# Atmaca.net
KiCad netlist of a schematic drawn in Altium Designer
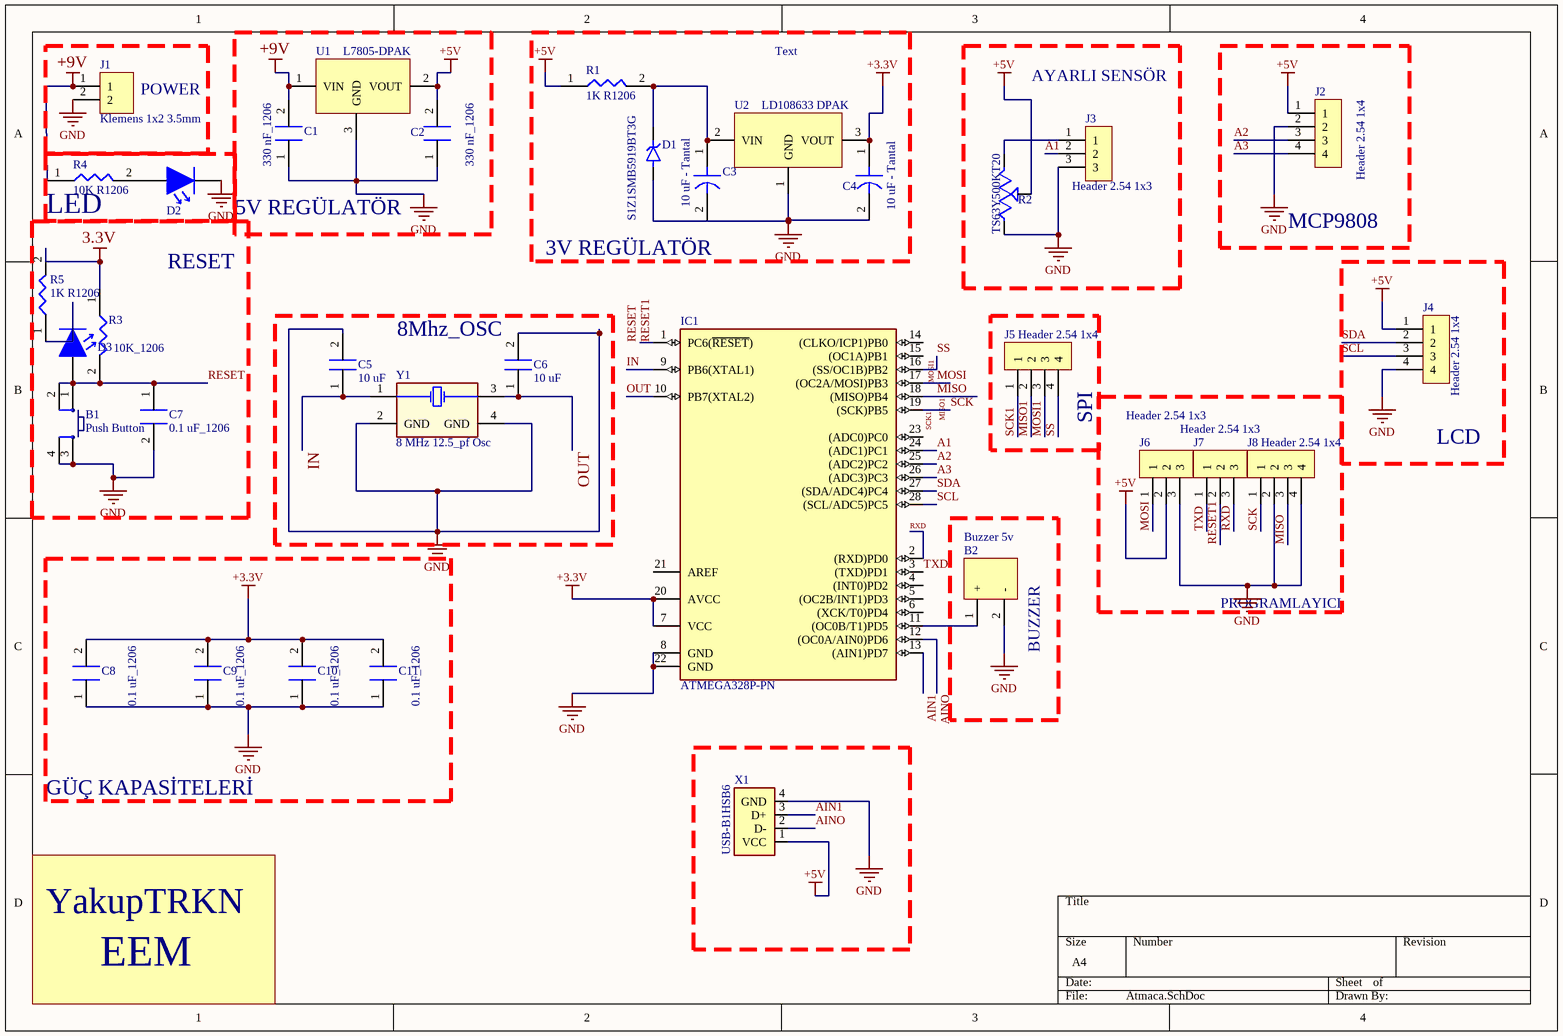
[diagram p0: Atmaca.SchDoc]

(export (version "E")
  (design (tool "Eeschema 10.0.6"))
  (components
    (comp (ref "B1")
      (value "Push Button")
      (footprint "PUSB BUTTON-SMD")
      (description "Smd Push Button")
      (libsource (lib "Staj") (part "Push Button"))
    )
    (comp (ref "B2")
      (value "Buzzer 5v")
      (footprint "Buzzer 5v")
      (libsource (lib "Atmaca") (part "Buzzer 5v"))
    )
    (comp (ref "C1")
      (value "330 nF_1206")
      (footprint "C1206")
      (description "330 nF C1206")
      (libsource (lib "Atmaca") (part "330 nF C1206"))
    )
    (comp (ref "C2")
      (value "330 nF_1206")
      (footprint "C1206")
      (description "330 nF C1206")
      (libsource (lib "Atmaca") (part "330 nF C1206"))
    )
    (comp (ref "C3")
      (value "10 uF - Tantal")
      (footprint "C1206- TANTAL")
      (libsource (lib "Atmaca") (part "10 uF - Tantal"))
    )
    (comp (ref "C4")
      (value "10 uF - Tantal")
      (footprint "C1206- TANTAL")
      (libsource (lib "Atmaca") (part "10 uF - Tantal"))
    )
    (comp (ref "C5") (value "10 uF") (footprint "C1206") (libsource (lib "Staj") (part "10 uF")))
    (comp (ref "C6") (value "10 uF") (footprint "C1206") (libsource (lib "Staj") (part "10 uF")))
    (comp (ref "C7")
      (value "0.1 uF_1206")
      (footprint "C1206")
      (description "0.1 uF C1206")
      (libsource (lib "Staj") (part "0.1 uF C1206"))
    )
    (comp (ref "C8")
      (value "0.1 uF_1206")
      (footprint "C1206")
      (description "0.1 uF C1206")
      (libsource (lib "Staj") (part "0.1 uF C1206"))
    )
    (comp (ref "C9")
      (value "0.1 uF_1206")
      (footprint "C1206")
      (description "0.1 uF C1206")
      (libsource (lib "Staj") (part "0.1 uF C1206"))
    )
    (comp (ref "C10")
      (value "0.1 uF_1206")
      (footprint "C1206")
      (description "0.1 uF C1206")
      (libsource (lib "Staj") (part "0.1 uF C1206"))
    )
    (comp (ref "C11")
      (value "0.1 uF_1206")
      (footprint "C1206")
      (description "0.1 uF C1206")
      (libsource (lib "Staj") (part "0.1 uF C1206"))
    )
    (comp (ref "D1")
      (value "S1Z1SMB5919BT3G")
      (footprint "S1Z1SMB5919BT3G:DIOM5436X247N")
      (description "Zener Diode 5.6V 3W Â±5% Surface Mount SMB")
      (fields (field (name "MF") "{'manufacturer': u'ON Semiconductor'}"))
      (libsource (lib "Atmaca") (part "S1Z1SMB5919BT3G"))
    )
    (comp (ref "D2")
      (value "LTST-C171GKT")
      (footprint "LED_GREEN_0805")
      (description "Green 0805 130 º Min 5 mcd Typical 12 mcd Water Clear Lens SMT LED")
      (fields (field (name "MANUFACTURER") "Vishay Lite-On") (field (name "DESIGNED BY") "BERK"))
      (libsource (lib "Atmaca") (part "LED GREEN 0805"))
    )
    (comp (ref "D3")
      (value "LH R974-LP-1")
      (footprint "LED_RED_0805")
      (description "LED Uni-Color Hyper Red 660nm 2-Pin Chip 0805(2012Metric) T/R")
      (fields (field (name "MANUFACTURER") "Osram Opto") (field (name "DESIGNED BY") "BERK"))
      (libsource (lib "Atmaca") (part "LED RED 0805"))
    )
    (comp (ref "IC1")
      (value "ATMEGA328P-PN")
      (footprint "ATMEGA328P-PN:DIL28")
      (description "Atmel ATmega48/88/168/328 AVR Microcontroller")
      (fields (field (name "MF") "{'manufacturer': u'Microchip'}"))
      (libsource (lib "Atmaca") (part "ATMEGA328P-PN"))
    )
    (comp (ref "J1")
      (value "Klemens 1x2 3.5mm")
      (footprint "Klemens 1x2 - 3.5mm")
      (libsource (lib "Atmaca") (part "Klemens 1x2 3.5mm"))
    )
    (comp (ref "J2")
      (value "Header 2.54 1x4")
      (footprint "Header 2.54 1x4")
      (libsource (lib "Atmaca") (part "Header 2.54 1x4"))
    )
    (comp (ref "J3")
      (value "Header 2.54 1x3")
      (footprint "Header 2.54 1x3")
      (libsource (lib "") (part "Header 2.54 1x3_1"))
    )
    (comp (ref "J4")
      (value "Header 2.54 1x4")
      (footprint "Header 2.54 1x4")
      (libsource (lib "Atmaca") (part "Header 2.54 1x4"))
    )
    (comp (ref "J5")
      (value "Header 2.54 1x4")
      (footprint "Header 2.54 1x4")
      (libsource (lib "") (part "Header 2.54 1x4_1"))
    )
    (comp (ref "J6")
      (value "Header 2.54 1x3")
      (footprint "Header 2.54 1x3")
      (libsource (lib "Atmaca") (part "Header 2.54 1x3"))
    )
    (comp (ref "J7")
      (value "Header 2.54 1x3")
      (footprint "Header 2.54 1x3")
      (libsource (lib "Atmaca") (part "Header 2.54 1x3"))
    )
    (comp (ref "J8")
      (value "Header 2.54 1x4")
      (footprint "Header 2.54 1x4")
      (libsource (lib "") (part "Header 2.54 1x4_1"))
    )
    (comp (ref "R1")
      (value "1K R1206")
      (footprint "R1206 Resıstor")
      (libsource (lib "Atmaca") (part "1K R1206"))
    )
    (comp (ref "R2")
      (value "TS63Y500KT20")
      (footprint "TS63Y500KT20:TRIM_TS63Y500KT20")
      (fields (field (name "MF") "{'manufacturer': u'Vishay Dale'}"))
      (libsource (lib "Atmaca") (part "TS63Y500KT20"))
    )
    (comp (ref "R3")
      (value "10K_1206")
      (footprint "R1206 Resıstor")
      (description "10K R1206")
      (libsource (lib "Staj") (part "10K R1206"))
    )
    (comp (ref "R4")
      (value "10K R1206")
      (footprint "R1206 Resıstor")
      (libsource (lib "Atmaca") (part "10K R1206"))
    )
    (comp (ref "R5")
      (value "1K R1206")
      (footprint "R1206 Resıstor")
      (libsource (lib "Atmaca") (part "1K R1206"))
    )
    (comp (ref "U1")
      (value "L7805-DPAK")
      (footprint "DPAK228P972X230-3N")
      (description "L7805 5V REGULATOR. SMD PAKET")
      (libsource (lib "Atmaca") (part "L7805-DPAK"))
    )
    (comp (ref "U2")
      (value "LD108633 DPAK")
      (footprint "DPAK228P972X230-3N")
      (description "LD1086 3.3V REGULATOR")
      (libsource (lib "Atmaca") (part "LD108633 DPAK"))
    )
    (comp (ref "X1")
      (value "USB-B1HSB6")
      (footprint "USB-B1HSB6:OST_USB-B1HSB6")
      (description "Conn Usb Type b r/a Black")
      (fields (field (name "MF") "{'manufacturer': u'On Shore'}"))
      (libsource (lib "Atmaca") (part "USB-B1HSB6"))
    )
    (comp (ref "Y1")
      (value "8 MHz 12.5_pf Osc")
      (footprint "8 MHZ Osc.")
      (description "8 MHz 12.5 pf Osc")
      (libsource (lib "Staj") (part "8 MHz 12.5 pf Osc"))
    )
  )
  (nets
    (net (code "1") (name "+3.3V") (class "Default")
      (node (ref "C10") (pin "2") (pinfunction "2_2") (pintype "passive"))
      (node (ref "C11") (pin "2") (pinfunction "2_2") (pintype "passive"))
      (node (ref "C4") (pin "1") (pinfunction "1_1") (pintype "passive"))
      (node (ref "C8") (pin "2") (pinfunction "2_2") (pintype "passive"))
      (node (ref "C9") (pin "2") (pinfunction "2_2") (pintype "passive"))
      (node (ref "IC1") (pin "20") (pinfunction "AVCC_20") (pintype "power_in"))
      (node (ref "IC1") (pin "7") (pinfunction "VCC_7") (pintype "power_in"))
      (node (ref "U2") (pin "3") (pinfunction "VOUT_3") (pintype "passive"))
    )
    (net (code "2") (name "+5V") (class "Default")
      (node (ref "C2") (pin "2") (pinfunction "2_2") (pintype "passive"))
      (node (ref "J2") (pin "1") (pinfunction "1_1") (pintype "passive"))
      (node (ref "J4") (pin "1") (pinfunction "1_1") (pintype "passive"))
      (node (ref "J6") (pin "2") (pinfunction "2_2") (pintype "passive"))
      (node (ref "R1") (pin "1") (pinfunction "1_1") (pintype "passive"))
      (node (ref "R2") (pin "2") (pinfunction "B_2") (pintype "passive"))
      (node (ref "U1") (pin "2") (pinfunction "VOUT_2") (pintype "passive"))
      (node (ref "X1") (pin "1") (pinfunction "VCC_1") (pintype "power_in"))
    )
    (net (code "3") (name "+9V") (class "Default")
      (node (ref "C1") (pin "2") (pinfunction "2_2") (pintype "passive"))
      (node (ref "J1") (pin "1") (pinfunction "1_1") (pintype "passive"))
      (node (ref "R4") (pin "1") (pinfunction "1_1") (pintype "passive"))
      (node (ref "U1") (pin "1") (pinfunction "VIN_1") (pintype "passive"))
    )
    (net (code "4") (name "/A1") (class "Default")
      (node (ref "IC1") (pin "24") (pinfunction "(ADC1)PC1_24") (pintype "bidirectional"))
      (node (ref "J3") (pin "2") (pinfunction "2_2") (pintype "passive"))
    )
    (net (code "5") (name "/A2") (class "Default")
      (node (ref "IC1") (pin "25") (pinfunction "(ADC2)PC2_25") (pintype "bidirectional"))
      (node (ref "J2") (pin "3") (pinfunction "3_3") (pintype "passive"))
    )
    (net (code "6") (name "/A3") (class "Default")
      (node (ref "IC1") (pin "26") (pinfunction "(ADC3)PC3_26") (pintype "bidirectional"))
      (node (ref "J2") (pin "4") (pinfunction "4_4") (pintype "passive"))
    )
    (net (code "7") (name "/AIN1") (class "Default")
      (node (ref "IC1") (pin "13") (pinfunction "(AIN1)PD7_13") (pintype "bidirectional"))
      (node (ref "X1") (pin "3") (pinfunction "D+_3") (pintype "bidirectional"))
    )
    (net (code "8") (name "/AINO") (class "Default")
      (node (ref "IC1") (pin "12") (pinfunction "(OC0A/AIN0)PD6_12") (pintype "bidirectional"))
      (node (ref "X1") (pin "2") (pinfunction "D-_2") (pintype "bidirectional"))
    )
    (net (code "9") (name "/IN") (class "Default")
      (node (ref "C5") (pin "1") (pinfunction "1_1") (pintype "passive"))
      (node (ref "IC1") (pin "9") (pinfunction "PB6(XTAL1)_9") (pintype "bidirectional"))
      (node (ref "Y1") (pin "1") (pintype "power_in"))
    )
    (net (code "10") (name "/MISO") (class "Default")
      (node (ref "IC1") (pin "18") (pinfunction "(MISO)PB4_18") (pintype "bidirectional"))
      (node (ref "J5") (pin "2") (pinfunction "2_2") (pintype "passive"))
      (node (ref "J8") (pin "3") (pinfunction "3_3") (pintype "passive"))
    )
    (net (code "11") (name "/MOSI") (class "Default")
      (node (ref "IC1") (pin "17") (pinfunction "(OC2A/MOSI)PB3_17") (pintype "bidirectional"))
      (node (ref "J5") (pin "3") (pinfunction "3_3") (pintype "passive"))
      (node (ref "J6") (pin "1") (pinfunction "1_1") (pintype "passive"))
    )
    (net (code "12") (name "/OUT") (class "Default")
      (node (ref "C6") (pin "1") (pinfunction "1_1") (pintype "passive"))
      (node (ref "IC1") (pin "10") (pinfunction "PB7(XTAL2)_10") (pintype "bidirectional"))
      (node (ref "Y1") (pin "3") (pintype "passive"))
    )
    (net (code "13") (name "/RESET") (class "Default")
      (node (ref "B1") (pin "1") (pinfunction "1_1") (pintype "passive"))
      (node (ref "B1") (pin "2") (pinfunction "2_2") (pintype "passive"))
      (node (ref "C7") (pin "1") (pinfunction "1_1") (pintype "passive"))
      (node (ref "D3") (pin "2") (pinfunction "2_2") (pintype "power_in"))
      (node (ref "IC1") (pin "1") (pinfunction "PC6(~{RESET})_1") (pintype "bidirectional"))
      (node (ref "J7") (pin "2") (pinfunction "2_2") (pintype "passive"))
      (node (ref "R3") (pin "2") (pinfunction "2_2") (pintype "passive"))
    )
    (net (code "14") (name "/RXD") (class "Default")
      (node (ref "IC1") (pin "2") (pinfunction "(RXD)PD0_2") (pintype "bidirectional"))
      (node (ref "J7") (pin "3") (pinfunction "3_3") (pintype "passive"))
    )
    (net (code "15") (name "/SCK") (class "Default")
      (node (ref "IC1") (pin "19") (pinfunction "(SCK)PB5_19") (pintype "bidirectional"))
      (node (ref "J5") (pin "1") (pinfunction "1_1") (pintype "passive"))
      (node (ref "J8") (pin "1") (pinfunction "1_1") (pintype "passive"))
    )
    (net (code "16") (name "/SCL") (class "Default")
      (node (ref "IC1") (pin "28") (pinfunction "(SCL/ADC5)PC5_28") (pintype "bidirectional"))
      (node (ref "J4") (pin "3") (pinfunction "3_3") (pintype "passive"))
    )
    (net (code "17") (name "/SDA") (class "Default")
      (node (ref "IC1") (pin "27") (pinfunction "(SDA/ADC4)PC4_27") (pintype "bidirectional"))
      (node (ref "J4") (pin "2") (pinfunction "2_2") (pintype "passive"))
    )
    (net (code "18") (name "/SS") (class "Default")
      (node (ref "IC1") (pin "16") (pinfunction "(SS/OC1B)PB2_16") (pintype "bidirectional"))
      (node (ref "J5") (pin "4") (pinfunction "4_4") (pintype "passive"))
    )
    (net (code "19") (name "/TXD") (class "Default")
      (node (ref "IC1") (pin "3") (pinfunction "(TXD)PD1_3") (pintype "bidirectional"))
      (node (ref "J7") (pin "1") (pinfunction "1_1") (pintype "passive"))
    )
    (net (code "20") (name "3.3V") (class "Default")
      (node (ref "R3") (pin "1") (pinfunction "1_1") (pintype "passive"))
      (node (ref "R5") (pin "2") (pinfunction "2_2") (pintype "passive"))
    )
    (net (code "21") (name "GND") (class "Default")
      (node (ref "B1") (pin "3") (pinfunction "3_3") (pintype "passive"))
      (node (ref "B1") (pin "4") (pinfunction "4_4") (pintype "passive"))
      (node (ref "B2") (pin "2") (pinfunction "-_2") (pintype "passive"))
      (node (ref "C1") (pin "1") (pinfunction "1_1") (pintype "passive"))
      (node (ref "C10") (pin "1") (pinfunction "1_1") (pintype "passive"))
      (node (ref "C11") (pin "1") (pinfunction "1_1") (pintype "passive"))
      (node (ref "C2") (pin "1") (pinfunction "1_1") (pintype "passive"))
      (node (ref "C4") (pin "2") (pinfunction "2_2") (pintype "passive"))
      (node (ref "C5") (pin "2") (pinfunction "2_2") (pintype "passive"))
      (node (ref "C6") (pin "2") (pinfunction "2_2") (pintype "passive"))
      (node (ref "C7") (pin "2") (pinfunction "2_2") (pintype "passive"))
      (node (ref "C8") (pin "1") (pinfunction "1_1") (pintype "passive"))
      (node (ref "C9") (pin "1") (pinfunction "1_1") (pintype "passive"))
      (node (ref "D1") (pin "A") (pinfunction "A_A") (pintype "passive"))
      (node (ref "D2") (pin "1") (pinfunction "1_1") (pintype "power_in"))
      (node (ref "IC1") (pin "22") (pinfunction "GND_22") (pintype "power_in"))
      (node (ref "IC1") (pin "8") (pinfunction "GND_8") (pintype "power_in"))
      (node (ref "J1") (pin "2") (pinfunction "2_2") (pintype "passive"))
      (node (ref "J2") (pin "2") (pinfunction "2_2") (pintype "passive"))
      (node (ref "J3") (pin "3") (pinfunction "3_3") (pintype "passive"))
      (node (ref "J4") (pin "4") (pinfunction "4_4") (pintype "passive"))
      (node (ref "J6") (pin "3") (pinfunction "3_3") (pintype "passive"))
      (node (ref "J8") (pin "2") (pinfunction "2_2") (pintype "passive"))
      (node (ref "J8") (pin "4") (pinfunction "4_4") (pintype "passive"))
      (node (ref "R2") (pin "1") (pinfunction "A_1") (pintype "passive"))
      (node (ref "U1") (pin "3") (pinfunction "GND_3") (pintype "passive"))
      (node (ref "U2") (pin "1") (pinfunction "GND_1") (pintype "passive"))
      (node (ref "X1") (pin "4") (pinfunction "GND_4") (pintype "power_in"))
      (node (ref "Y1") (pin "2") (pinfunction "GND_2") (pintype "power_in"))
      (node (ref "Y1") (pin "4") (pinfunction "GND_4") (pintype "passive"))
    )
    (net (code "22") (name "Net-(B2-+)") (class "Default")
      (node (ref "B2") (pin "1") (pinfunction "+_1") (pintype "passive"))
      (node (ref "IC1") (pin "11") (pinfunction "(OC0B/T1)PD5_11") (pintype "bidirectional"))
    )
    (net (code "23") (name "Net-(D1-K)") (class "Default")
      (node (ref "C3") (pin "1") (pinfunction "1_1") (pintype "passive"))
      (node (ref "D1") (pin "C") (pinfunction "K_C") (pintype "passive"))
      (node (ref "R1") (pin "2") (pinfunction "2_2") (pintype "passive"))
      (node (ref "U2") (pin "2") (pinfunction "VIN_2") (pintype "passive"))
    )
    (net (code "24") (name "Net-(D2-Pad2)") (class "Default")
      (node (ref "D2") (pin "2") (pinfunction "2_2") (pintype "power_in"))
      (node (ref "R4") (pin "2") (pinfunction "2_2") (pintype "passive"))
    )
    (net (code "25") (name "Net-(D3-Pad1)") (class "Default")
      (node (ref "D3") (pin "1") (pinfunction "1_1") (pintype "power_in"))
      (node (ref "R5") (pin "1") (pinfunction "1_1") (pintype "passive"))
    )
    (net (code "26") (name "Net-(R2-C)") (class "Default")
      (node (ref "J3") (pin "1") (pinfunction "1_1") (pintype "passive"))
      (node (ref "R2") (pin "3") (pinfunction "C_3") (pintype "passive"))
    )
    (net (code "27") (name "unconnected-(C3-Pad2)") (class "Default")
      (node (ref "C3") (pin "2") (pinfunction "2_2") (pintype "passive"))
    )
    (net (code "28") (name "unconnected-(IC1-(ADC0)PC0-Pad23)") (class "Default")
      (node (ref "IC1") (pin "23") (pinfunction "(ADC0)PC0_23") (pintype "bidirectional"))
    )
    (net (code "29") (name "unconnected-(IC1-(CLKO{slash}ICP1)PB0-Pad14)") (class "Default")
      (node (ref "IC1") (pin "14") (pinfunction "(CLKO/ICP1)PB0_14") (pintype "bidirectional"))
    )
    (net (code "30") (name "unconnected-(IC1-(INT0)PD2-Pad4)") (class "Default")
      (node (ref "IC1") (pin "4") (pinfunction "(INT0)PD2_4") (pintype "bidirectional"))
    )
    (net (code "31") (name "unconnected-(IC1-(OC1A)PB1-Pad15)") (class "Default")
      (node (ref "IC1") (pin "15") (pinfunction "(OC1A)PB1_15") (pintype "bidirectional"))
    )
    (net (code "32") (name "unconnected-(IC1-(OC2B{slash}INT1)PD3-Pad5)") (class "Default")
      (node (ref "IC1") (pin "5") (pinfunction "(OC2B/INT1)PD3_5") (pintype "bidirectional"))
    )
    (net (code "33") (name "unconnected-(IC1-(XCK{slash}T0)PD4-Pad6)") (class "Default")
      (node (ref "IC1") (pin "6") (pinfunction "(XCK/T0)PD4_6") (pintype "bidirectional"))
    )
    (net (code "34") (name "unconnected-(IC1-AREF-Pad21)") (class "Default")
      (node (ref "IC1") (pin "21") (pinfunction "AREF_21") (pintype "passive"))
    )
  )
)
